# shift_reg.net
KiCad netlist of a schematic drawn in EAGLE
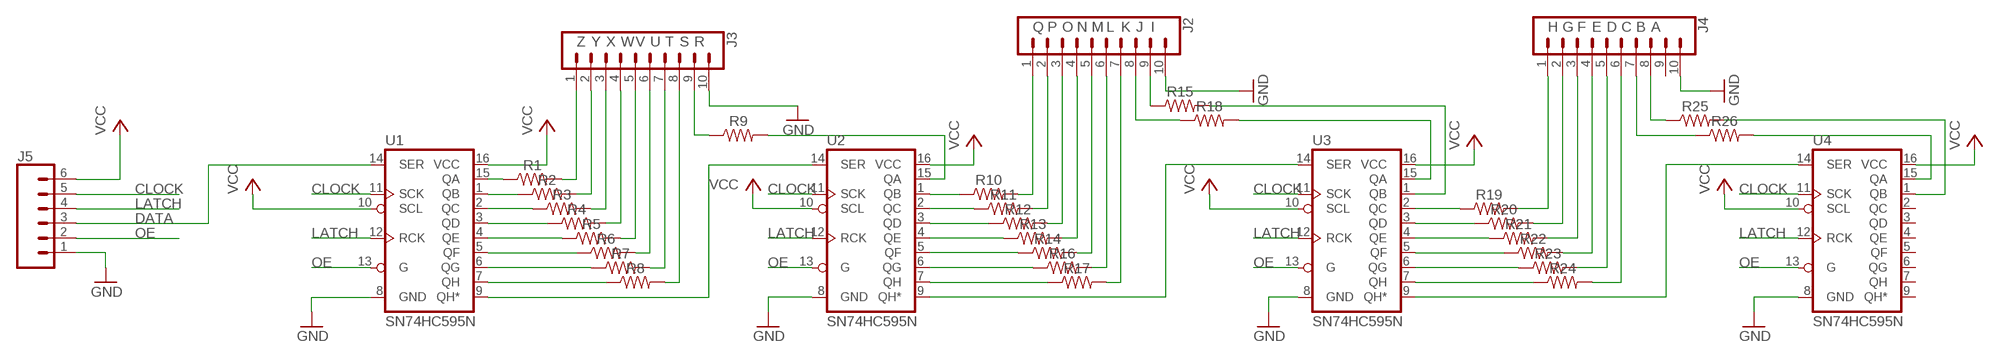
[diagram p0: schematic, sheet 1]

(export (version "E")
  (design (tool "Eeschema 10.0.6"))
  (components
    (comp (ref "J2")
      (value "CONN_10\"")
      (footprint "eagle-import:1X10")
      (libsource (lib "eagle-import") (part "CONN_10{dblquote}"))
    )
    (comp (ref "J3")
      (value "CONN_10\"")
      (footprint "eagle-import:1X10")
      (libsource (lib "eagle-import") (part "CONN_10{dblquote}"))
    )
    (comp (ref "J4")
      (value "CONN_10\"")
      (footprint "eagle-import:1X10")
      (libsource (lib "eagle-import") (part "CONN_10{dblquote}"))
    )
    (comp (ref "J5")
      (value "CONN_06LOCK")
      (footprint "eagle-import:1X06_LOCK")
      (libsource (lib "eagle-import") (part "CONN_06LOCK"))
    )
    (comp (ref "R1")
      (value "RESISTORAXIAL-0.3")
      (footprint "eagle-import:AXIAL-0.3")
      (libsource (lib "eagle-import") (part "RESISTORAXIAL-0.3"))
    )
    (comp (ref "R2")
      (value "RESISTORAXIAL-0.3")
      (footprint "eagle-import:AXIAL-0.3")
      (libsource (lib "eagle-import") (part "RESISTORAXIAL-0.3"))
    )
    (comp (ref "R3")
      (value "RESISTORAXIAL-0.3")
      (footprint "eagle-import:AXIAL-0.3")
      (libsource (lib "eagle-import") (part "RESISTORAXIAL-0.3"))
    )
    (comp (ref "R4")
      (value "RESISTORAXIAL-0.3")
      (footprint "eagle-import:AXIAL-0.3")
      (libsource (lib "eagle-import") (part "RESISTORAXIAL-0.3"))
    )
    (comp (ref "R5")
      (value "RESISTORAXIAL-0.3")
      (footprint "eagle-import:AXIAL-0.3")
      (libsource (lib "eagle-import") (part "RESISTORAXIAL-0.3"))
    )
    (comp (ref "R6")
      (value "RESISTORAXIAL-0.3")
      (footprint "eagle-import:AXIAL-0.3")
      (libsource (lib "eagle-import") (part "RESISTORAXIAL-0.3"))
    )
    (comp (ref "R7")
      (value "RESISTORAXIAL-0.3")
      (footprint "eagle-import:AXIAL-0.3")
      (libsource (lib "eagle-import") (part "RESISTORAXIAL-0.3"))
    )
    (comp (ref "R8")
      (value "RESISTORAXIAL-0.3")
      (footprint "eagle-import:AXIAL-0.3")
      (libsource (lib "eagle-import") (part "RESISTORAXIAL-0.3"))
    )
    (comp (ref "R9")
      (value "RESISTORAXIAL-0.3")
      (footprint "eagle-import:AXIAL-0.3")
      (libsource (lib "eagle-import") (part "RESISTORAXIAL-0.3"))
    )
    (comp (ref "R10")
      (value "RESISTORAXIAL-0.3")
      (footprint "eagle-import:AXIAL-0.3")
      (libsource (lib "eagle-import") (part "RESISTORAXIAL-0.3"))
    )
    (comp (ref "R11")
      (value "RESISTORAXIAL-0.3")
      (footprint "eagle-import:AXIAL-0.3")
      (libsource (lib "eagle-import") (part "RESISTORAXIAL-0.3"))
    )
    (comp (ref "R12")
      (value "RESISTORAXIAL-0.3")
      (footprint "eagle-import:AXIAL-0.3")
      (libsource (lib "eagle-import") (part "RESISTORAXIAL-0.3"))
    )
    (comp (ref "R13")
      (value "RESISTORAXIAL-0.3")
      (footprint "eagle-import:AXIAL-0.3")
      (libsource (lib "eagle-import") (part "RESISTORAXIAL-0.3"))
    )
    (comp (ref "R14")
      (value "RESISTORAXIAL-0.3")
      (footprint "eagle-import:AXIAL-0.3")
      (libsource (lib "eagle-import") (part "RESISTORAXIAL-0.3"))
    )
    (comp (ref "R15")
      (value "RESISTORAXIAL-0.3")
      (footprint "eagle-import:AXIAL-0.3")
      (libsource (lib "eagle-import") (part "RESISTORAXIAL-0.3"))
    )
    (comp (ref "R16")
      (value "RESISTORAXIAL-0.3")
      (footprint "eagle-import:AXIAL-0.3")
      (libsource (lib "eagle-import") (part "RESISTORAXIAL-0.3"))
    )
    (comp (ref "R17")
      (value "RESISTORAXIAL-0.3")
      (footprint "eagle-import:AXIAL-0.3")
      (libsource (lib "eagle-import") (part "RESISTORAXIAL-0.3"))
    )
    (comp (ref "R18")
      (value "RESISTORAXIAL-0.3")
      (footprint "eagle-import:AXIAL-0.3")
      (libsource (lib "eagle-import") (part "RESISTORAXIAL-0.3"))
    )
    (comp (ref "R19")
      (value "RESISTORAXIAL-0.3")
      (footprint "eagle-import:AXIAL-0.3")
      (libsource (lib "eagle-import") (part "RESISTORAXIAL-0.3"))
    )
    (comp (ref "R20")
      (value "RESISTORAXIAL-0.3")
      (footprint "eagle-import:AXIAL-0.3")
      (libsource (lib "eagle-import") (part "RESISTORAXIAL-0.3"))
    )
    (comp (ref "R21")
      (value "RESISTORAXIAL-0.3")
      (footprint "eagle-import:AXIAL-0.3")
      (libsource (lib "eagle-import") (part "RESISTORAXIAL-0.3"))
    )
    (comp (ref "R22")
      (value "RESISTORAXIAL-0.3")
      (footprint "eagle-import:AXIAL-0.3")
      (libsource (lib "eagle-import") (part "RESISTORAXIAL-0.3"))
    )
    (comp (ref "R23")
      (value "RESISTORAXIAL-0.3")
      (footprint "eagle-import:AXIAL-0.3")
      (libsource (lib "eagle-import") (part "RESISTORAXIAL-0.3"))
    )
    (comp (ref "R24")
      (value "RESISTORAXIAL-0.3")
      (footprint "eagle-import:AXIAL-0.3")
      (libsource (lib "eagle-import") (part "RESISTORAXIAL-0.3"))
    )
    (comp (ref "R25")
      (value "RESISTORAXIAL-0.3")
      (footprint "eagle-import:AXIAL-0.3")
      (libsource (lib "eagle-import") (part "RESISTORAXIAL-0.3"))
    )
    (comp (ref "R26")
      (value "RESISTORAXIAL-0.3")
      (footprint "eagle-import:AXIAL-0.3")
      (libsource (lib "eagle-import") (part "RESISTORAXIAL-0.3"))
    )
    (comp (ref "U1")
      (value "SN74HC595N")
      (footprint "eagle-import:DIP16")
      (libsource (lib "eagle-import") (part "74595NHC"))
    )
    (comp (ref "U2")
      (value "SN74HC595N")
      (footprint "eagle-import:DIP16")
      (libsource (lib "eagle-import") (part "74595NHC"))
    )
    (comp (ref "U3")
      (value "SN74HC595N")
      (footprint "eagle-import:DIP16")
      (libsource (lib "eagle-import") (part "74595NHC"))
    )
    (comp (ref "U4")
      (value "SN74HC595N")
      (footprint "eagle-import:DIP16")
      (libsource (lib "eagle-import") (part "74595NHC"))
    )
  )
  (nets
    (net (code "1") (name "/A") (class "Default")
      (node (ref "J4") (pin "8") (pinfunction "8_8") (pintype "passive"))
      (node (ref "R25") (pin "P$1") (pinfunction "1_P$1") (pintype "passive"))
    )
    (net (code "2") (name "/B") (class "Default")
      (node (ref "J4") (pin "7") (pinfunction "7_7") (pintype "passive"))
      (node (ref "R26") (pin "P$1") (pinfunction "1_P$1") (pintype "passive"))
    )
    (net (code "3") (name "/C") (class "Default")
      (node (ref "J4") (pin "6") (pinfunction "6_6") (pintype "passive"))
      (node (ref "R24") (pin "P$2") (pinfunction "2_P$2") (pintype "passive"))
    )
    (net (code "4") (name "/CLOCK") (class "Default")
      (node (ref "J5") (pin "5") (pinfunction "5_5") (pintype "passive"))
      (node (ref "U1") (pin "11") (pinfunction "SCK_11") (pintype "input"))
      (node (ref "U2") (pin "11") (pinfunction "SCK_11") (pintype "input"))
      (node (ref "U3") (pin "11") (pinfunction "SCK_11") (pintype "input"))
      (node (ref "U4") (pin "11") (pinfunction "SCK_11") (pintype "input"))
    )
    (net (code "5") (name "/D") (class "Default")
      (node (ref "J4") (pin "5") (pinfunction "5_5") (pintype "passive"))
      (node (ref "R23") (pin "P$2") (pinfunction "2_P$2") (pintype "passive"))
    )
    (net (code "6") (name "/DATA") (class "Default")
      (node (ref "J5") (pin "3") (pinfunction "3_3") (pintype "passive"))
      (node (ref "U1") (pin "14") (pinfunction "SER_14") (pintype "input"))
    )
    (net (code "7") (name "/E") (class "Default")
      (node (ref "J4") (pin "4") (pinfunction "4_4") (pintype "passive"))
      (node (ref "R22") (pin "P$2") (pinfunction "2_P$2") (pintype "passive"))
    )
    (net (code "8") (name "/F") (class "Default")
      (node (ref "J4") (pin "3") (pinfunction "3_3") (pintype "passive"))
      (node (ref "R21") (pin "P$2") (pinfunction "2_P$2") (pintype "passive"))
    )
    (net (code "9") (name "/G") (class "Default")
      (node (ref "J4") (pin "2") (pinfunction "2_2") (pintype "passive"))
      (node (ref "R20") (pin "P$2") (pinfunction "2_P$2") (pintype "passive"))
    )
    (net (code "10") (name "/H") (class "Default")
      (node (ref "J4") (pin "1") (pinfunction "1_1") (pintype "passive"))
      (node (ref "R19") (pin "P$2") (pinfunction "2_P$2") (pintype "passive"))
    )
    (net (code "11") (name "/I") (class "Default")
      (node (ref "J2") (pin "9") (pinfunction "9_9") (pintype "passive"))
      (node (ref "R15") (pin "P$1") (pinfunction "1_P$1") (pintype "passive"))
    )
    (net (code "12") (name "/J") (class "Default")
      (node (ref "J2") (pin "8") (pinfunction "8_8") (pintype "passive"))
      (node (ref "R18") (pin "P$1") (pinfunction "1_P$1") (pintype "passive"))
    )
    (net (code "13") (name "/K") (class "Default")
      (node (ref "J2") (pin "7") (pinfunction "7_7") (pintype "passive"))
      (node (ref "R17") (pin "P$2") (pinfunction "2_P$2") (pintype "passive"))
    )
    (net (code "14") (name "/L") (class "Default")
      (node (ref "J2") (pin "6") (pinfunction "6_6") (pintype "passive"))
      (node (ref "R16") (pin "P$2") (pinfunction "2_P$2") (pintype "passive"))
    )
    (net (code "15") (name "/LATCH") (class "Default")
      (node (ref "J5") (pin "4") (pinfunction "4_4") (pintype "passive"))
      (node (ref "U1") (pin "12") (pinfunction "RCK_12") (pintype "input"))
      (node (ref "U2") (pin "12") (pinfunction "RCK_12") (pintype "input"))
      (node (ref "U3") (pin "12") (pinfunction "RCK_12") (pintype "input"))
      (node (ref "U4") (pin "12") (pinfunction "RCK_12") (pintype "input"))
    )
    (net (code "16") (name "/M") (class "Default")
      (node (ref "J2") (pin "5") (pinfunction "5_5") (pintype "passive"))
      (node (ref "R14") (pin "P$2") (pinfunction "2_P$2") (pintype "passive"))
    )
    (net (code "17") (name "/N") (class "Default")
      (node (ref "J2") (pin "4") (pinfunction "4_4") (pintype "passive"))
      (node (ref "R13") (pin "P$2") (pinfunction "2_P$2") (pintype "passive"))
    )
    (net (code "18") (name "/O") (class "Default")
      (node (ref "J2") (pin "3") (pinfunction "3_3") (pintype "passive"))
      (node (ref "R12") (pin "P$2") (pinfunction "2_P$2") (pintype "passive"))
    )
    (net (code "19") (name "/OE") (class "Default")
      (node (ref "J5") (pin "2") (pinfunction "2_2") (pintype "passive"))
      (node (ref "U1") (pin "13") (pinfunction "G_13") (pintype "input"))
      (node (ref "U2") (pin "13") (pinfunction "G_13") (pintype "input"))
      (node (ref "U3") (pin "13") (pinfunction "G_13") (pintype "input"))
      (node (ref "U4") (pin "13") (pinfunction "G_13") (pintype "input"))
    )
    (net (code "20") (name "/P") (class "Default")
      (node (ref "J2") (pin "2") (pinfunction "2_2") (pintype "passive"))
      (node (ref "R11") (pin "P$2") (pinfunction "2_P$2") (pintype "passive"))
    )
    (net (code "21") (name "/Q") (class "Default")
      (node (ref "J2") (pin "1") (pinfunction "1_1") (pintype "passive"))
      (node (ref "R10") (pin "P$2") (pinfunction "2_P$2") (pintype "passive"))
    )
    (net (code "22") (name "/R") (class "Default")
      (node (ref "J3") (pin "9") (pinfunction "9_9") (pintype "passive"))
      (node (ref "R9") (pin "P$1") (pinfunction "1_P$1") (pintype "passive"))
    )
    (net (code "23") (name "/S") (class "Default")
      (node (ref "J3") (pin "8") (pinfunction "8_8") (pintype "passive"))
      (node (ref "R8") (pin "P$2") (pinfunction "2_P$2") (pintype "passive"))
    )
    (net (code "24") (name "/T") (class "Default")
      (node (ref "J3") (pin "7") (pinfunction "7_7") (pintype "passive"))
      (node (ref "R7") (pin "P$2") (pinfunction "2_P$2") (pintype "passive"))
    )
    (net (code "25") (name "/U") (class "Default")
      (node (ref "J3") (pin "6") (pinfunction "6_6") (pintype "passive"))
      (node (ref "R6") (pin "P$2") (pinfunction "2_P$2") (pintype "passive"))
    )
    (net (code "26") (name "/V") (class "Default")
      (node (ref "J3") (pin "5") (pinfunction "5_5") (pintype "passive"))
      (node (ref "R5") (pin "P$2") (pinfunction "2_P$2") (pintype "passive"))
    )
    (net (code "27") (name "/W") (class "Default")
      (node (ref "J3") (pin "4") (pinfunction "4_4") (pintype "passive"))
      (node (ref "R4") (pin "P$2") (pinfunction "2_P$2") (pintype "passive"))
    )
    (net (code "28") (name "/X") (class "Default")
      (node (ref "J3") (pin "3") (pinfunction "3_3") (pintype "passive"))
      (node (ref "R3") (pin "P$2") (pinfunction "2_P$2") (pintype "passive"))
    )
    (net (code "29") (name "/Y") (class "Default")
      (node (ref "J3") (pin "2") (pinfunction "2_2") (pintype "passive"))
      (node (ref "R2") (pin "P$2") (pinfunction "2_P$2") (pintype "passive"))
    )
    (net (code "30") (name "/Z") (class "Default")
      (node (ref "J3") (pin "1") (pinfunction "1_1") (pintype "passive"))
      (node (ref "R1") (pin "P$2") (pinfunction "2_P$2") (pintype "passive"))
    )
    (net (code "31") (name "GND") (class "Default")
      (node (ref "J2") (pin "10") (pinfunction "10_10") (pintype "passive"))
      (node (ref "J3") (pin "10") (pinfunction "10_10") (pintype "passive"))
      (node (ref "J4") (pin "10") (pinfunction "10_10") (pintype "passive"))
      (node (ref "J5") (pin "1") (pinfunction "1_1") (pintype "passive"))
      (node (ref "U1") (pin "8") (pinfunction "GND_8") (pintype "power_in"))
      (node (ref "U2") (pin "8") (pinfunction "GND_8") (pintype "power_in"))
      (node (ref "U3") (pin "8") (pinfunction "GND_8") (pintype "power_in"))
      (node (ref "U4") (pin "8") (pinfunction "GND_8") (pintype "power_in"))
    )
    (net (code "32") (name "Net-(R1-1)") (class "Default")
      (node (ref "R1") (pin "P$1") (pinfunction "1_P$1") (pintype "passive"))
      (node (ref "U1") (pin "15") (pinfunction "QA_15") (pintype "tri_state"))
    )
    (net (code "33") (name "Net-(R2-1)") (class "Default")
      (node (ref "R2") (pin "P$1") (pinfunction "1_P$1") (pintype "passive"))
      (node (ref "U1") (pin "1") (pinfunction "QB_1") (pintype "tri_state"))
    )
    (net (code "34") (name "Net-(R3-1)") (class "Default")
      (node (ref "R3") (pin "P$1") (pinfunction "1_P$1") (pintype "passive"))
      (node (ref "U1") (pin "2") (pinfunction "QC_2") (pintype "tri_state"))
    )
    (net (code "35") (name "Net-(R4-1)") (class "Default")
      (node (ref "R4") (pin "P$1") (pinfunction "1_P$1") (pintype "passive"))
      (node (ref "U1") (pin "3") (pinfunction "QD_3") (pintype "tri_state"))
    )
    (net (code "36") (name "Net-(R5-1)") (class "Default")
      (node (ref "R5") (pin "P$1") (pinfunction "1_P$1") (pintype "passive"))
      (node (ref "U1") (pin "4") (pinfunction "QE_4") (pintype "tri_state"))
    )
    (net (code "37") (name "Net-(R6-1)") (class "Default")
      (node (ref "R6") (pin "P$1") (pinfunction "1_P$1") (pintype "passive"))
      (node (ref "U1") (pin "5") (pinfunction "QF_5") (pintype "tri_state"))
    )
    (net (code "38") (name "Net-(R7-1)") (class "Default")
      (node (ref "R7") (pin "P$1") (pinfunction "1_P$1") (pintype "passive"))
      (node (ref "U1") (pin "6") (pinfunction "QG_6") (pintype "tri_state"))
    )
    (net (code "39") (name "Net-(R8-1)") (class "Default")
      (node (ref "R8") (pin "P$1") (pinfunction "1_P$1") (pintype "passive"))
      (node (ref "U1") (pin "7") (pinfunction "QH_7") (pintype "tri_state"))
    )
    (net (code "40") (name "Net-(R9-2)") (class "Default")
      (node (ref "R9") (pin "P$2") (pinfunction "2_P$2") (pintype "passive"))
      (node (ref "U2") (pin "15") (pinfunction "QA_15") (pintype "tri_state"))
    )
    (net (code "41") (name "Net-(R10-1)") (class "Default")
      (node (ref "R10") (pin "P$1") (pinfunction "1_P$1") (pintype "passive"))
      (node (ref "U2") (pin "1") (pinfunction "QB_1") (pintype "tri_state"))
    )
    (net (code "42") (name "Net-(R11-1)") (class "Default")
      (node (ref "R11") (pin "P$1") (pinfunction "1_P$1") (pintype "passive"))
      (node (ref "U2") (pin "2") (pinfunction "QC_2") (pintype "tri_state"))
    )
    (net (code "43") (name "Net-(R12-1)") (class "Default")
      (node (ref "R12") (pin "P$1") (pinfunction "1_P$1") (pintype "passive"))
      (node (ref "U2") (pin "3") (pinfunction "QD_3") (pintype "tri_state"))
    )
    (net (code "44") (name "Net-(R13-1)") (class "Default")
      (node (ref "R13") (pin "P$1") (pinfunction "1_P$1") (pintype "passive"))
      (node (ref "U2") (pin "4") (pinfunction "QE_4") (pintype "tri_state"))
    )
    (net (code "45") (name "Net-(R14-1)") (class "Default")
      (node (ref "R14") (pin "P$1") (pinfunction "1_P$1") (pintype "passive"))
      (node (ref "U2") (pin "5") (pinfunction "QF_5") (pintype "tri_state"))
    )
    (net (code "46") (name "Net-(R15-2)") (class "Default")
      (node (ref "R15") (pin "P$2") (pinfunction "2_P$2") (pintype "passive"))
      (node (ref "U3") (pin "1") (pinfunction "QB_1") (pintype "tri_state"))
    )
    (net (code "47") (name "Net-(R16-1)") (class "Default")
      (node (ref "R16") (pin "P$1") (pinfunction "1_P$1") (pintype "passive"))
      (node (ref "U2") (pin "6") (pinfunction "QG_6") (pintype "tri_state"))
    )
    (net (code "48") (name "Net-(R17-1)") (class "Default")
      (node (ref "R17") (pin "P$1") (pinfunction "1_P$1") (pintype "passive"))
      (node (ref "U2") (pin "7") (pinfunction "QH_7") (pintype "tri_state"))
    )
    (net (code "49") (name "Net-(R18-2)") (class "Default")
      (node (ref "R18") (pin "P$2") (pinfunction "2_P$2") (pintype "passive"))
      (node (ref "U3") (pin "15") (pinfunction "QA_15") (pintype "tri_state"))
    )
    (net (code "50") (name "Net-(R19-1)") (class "Default")
      (node (ref "R19") (pin "P$1") (pinfunction "1_P$1") (pintype "passive"))
      (node (ref "U3") (pin "2") (pinfunction "QC_2") (pintype "tri_state"))
    )
    (net (code "51") (name "Net-(R20-1)") (class "Default")
      (node (ref "R20") (pin "P$1") (pinfunction "1_P$1") (pintype "passive"))
      (node (ref "U3") (pin "3") (pinfunction "QD_3") (pintype "tri_state"))
    )
    (net (code "52") (name "Net-(R21-1)") (class "Default")
      (node (ref "R21") (pin "P$1") (pinfunction "1_P$1") (pintype "passive"))
      (node (ref "U3") (pin "4") (pinfunction "QE_4") (pintype "tri_state"))
    )
    (net (code "53") (name "Net-(R22-1)") (class "Default")
      (node (ref "R22") (pin "P$1") (pinfunction "1_P$1") (pintype "passive"))
      (node (ref "U3") (pin "5") (pinfunction "QF_5") (pintype "tri_state"))
    )
    (net (code "54") (name "Net-(R23-1)") (class "Default")
      (node (ref "R23") (pin "P$1") (pinfunction "1_P$1") (pintype "passive"))
      (node (ref "U3") (pin "6") (pinfunction "QG_6") (pintype "tri_state"))
    )
    (net (code "55") (name "Net-(R24-1)") (class "Default")
      (node (ref "R24") (pin "P$1") (pinfunction "1_P$1") (pintype "passive"))
      (node (ref "U3") (pin "7") (pinfunction "QH_7") (pintype "tri_state"))
    )
    (net (code "56") (name "Net-(R25-2)") (class "Default")
      (node (ref "R25") (pin "P$2") (pinfunction "2_P$2") (pintype "passive"))
      (node (ref "U4") (pin "1") (pinfunction "QB_1") (pintype "tri_state"))
    )
    (net (code "57") (name "Net-(R26-2)") (class "Default")
      (node (ref "R26") (pin "P$2") (pinfunction "2_P$2") (pintype "passive"))
      (node (ref "U4") (pin "15") (pinfunction "QA_15") (pintype "tri_state"))
    )
    (net (code "58") (name "Net-(U1-QH*)") (class "Default")
      (node (ref "U1") (pin "9") (pinfunction "QH*_9") (pintype "tri_state"))
      (node (ref "U2") (pin "14") (pinfunction "SER_14") (pintype "input"))
    )
    (net (code "59") (name "Net-(U2-QH*)") (class "Default")
      (node (ref "U2") (pin "9") (pinfunction "QH*_9") (pintype "tri_state"))
      (node (ref "U3") (pin "14") (pinfunction "SER_14") (pintype "input"))
    )
    (net (code "60") (name "Net-(U3-QH*)") (class "Default")
      (node (ref "U3") (pin "9") (pinfunction "QH*_9") (pintype "tri_state"))
      (node (ref "U4") (pin "14") (pinfunction "SER_14") (pintype "input"))
    )
    (net (code "61") (name "VCC") (class "Default")
      (node (ref "J5") (pin "6") (pinfunction "6_6") (pintype "passive"))
      (node (ref "U1") (pin "10") (pinfunction "SCL_10") (pintype "input"))
      (node (ref "U1") (pin "16") (pinfunction "VCC_16") (pintype "power_in"))
      (node (ref "U2") (pin "10") (pinfunction "SCL_10") (pintype "input"))
      (node (ref "U2") (pin "16") (pinfunction "VCC_16") (pintype "power_in"))
      (node (ref "U3") (pin "10") (pinfunction "SCL_10") (pintype "input"))
      (node (ref "U3") (pin "16") (pinfunction "VCC_16") (pintype "power_in"))
      (node (ref "U4") (pin "10") (pinfunction "SCL_10") (pintype "input"))
      (node (ref "U4") (pin "16") (pinfunction "VCC_16") (pintype "power_in"))
    )
    (net (code "62") (name "unconnected-(J4-Pad9)") (class "Default")
      (node (ref "J4") (pin "9") (pinfunction "9_9") (pintype "passive"))
    )
    (net (code "63") (name "unconnected-(U4-QC-Pad2)") (class "Default")
      (node (ref "U4") (pin "2") (pinfunction "QC_2") (pintype "tri_state"))
    )
    (net (code "64") (name "unconnected-(U4-QD-Pad3)") (class "Default")
      (node (ref "U4") (pin "3") (pinfunction "QD_3") (pintype "tri_state"))
    )
    (net (code "65") (name "unconnected-(U4-QE-Pad4)") (class "Default")
      (node (ref "U4") (pin "4") (pinfunction "QE_4") (pintype "tri_state"))
    )
    (net (code "66") (name "unconnected-(U4-QF-Pad5)") (class "Default")
      (node (ref "U4") (pin "5") (pinfunction "QF_5") (pintype "tri_state"))
    )
    (net (code "67") (name "unconnected-(U4-QG-Pad6)") (class "Default")
      (node (ref "U4") (pin "6") (pinfunction "QG_6") (pintype "tri_state"))
    )
    (net (code "68") (name "unconnected-(U4-QH*-Pad9)") (class "Default")
      (node (ref "U4") (pin "9") (pinfunction "QH*_9") (pintype "tri_state"))
    )
    (net (code "69") (name "unconnected-(U4-QH-Pad7)") (class "Default")
      (node (ref "U4") (pin "7") (pinfunction "QH_7") (pintype "tri_state"))
    )
  )
)
